# CAN_Bus.net
KiCad netlist of a schematic drawn in EAGLE
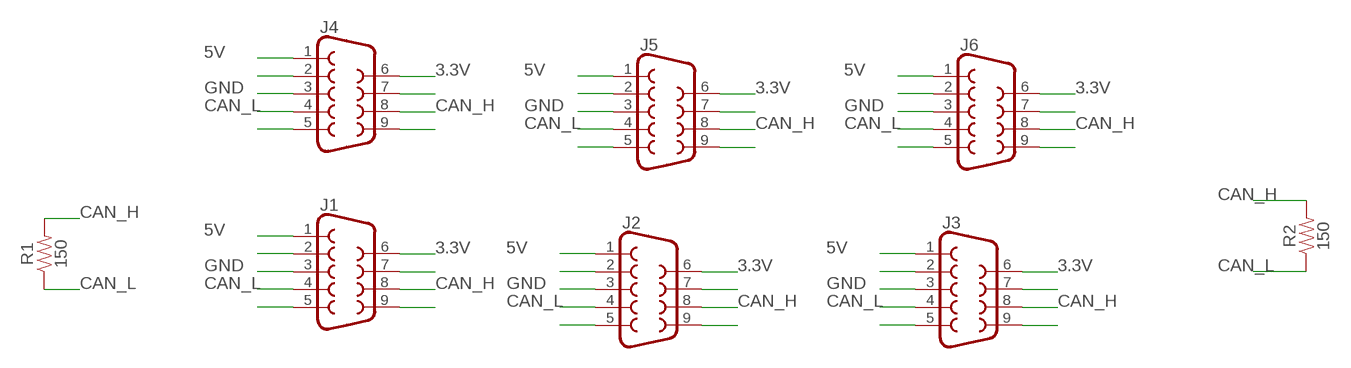
[diagram p0: schematic, sheet 1]

(export (version "E")
  (design (tool "Eeschema 10.0.6"))
  (components
    (comp (ref "J1")
      (value "DB9FEMALE")
      (footprint "eagle-import:DB9")
      (libsource (lib "eagle-import") (part "DB9FEMALE"))
    )
    (comp (ref "J2")
      (value "DB9FEMALE")
      (footprint "eagle-import:DB9")
      (libsource (lib "eagle-import") (part "DB9FEMALE"))
    )
    (comp (ref "J3")
      (value "DB9FEMALE")
      (footprint "eagle-import:DB9")
      (libsource (lib "eagle-import") (part "DB9FEMALE"))
    )
    (comp (ref "J4")
      (value "DB9FEMALE")
      (footprint "eagle-import:DB9")
      (libsource (lib "eagle-import") (part "DB9FEMALE"))
    )
    (comp (ref "J5")
      (value "DB9FEMALE")
      (footprint "eagle-import:DB9")
      (libsource (lib "eagle-import") (part "DB9FEMALE"))
    )
    (comp (ref "J6")
      (value "DB9FEMALE")
      (footprint "eagle-import:DB9")
      (libsource (lib "eagle-import") (part "DB9FEMALE"))
    )
    (comp (ref "R1")
      (value "150")
      (footprint "eagle-import:AXIAL-0.3")
      (libsource (lib "eagle-import") (part "100OHM-HORIZ-1/4W-1%"))
    )
    (comp (ref "R2")
      (value "150")
      (footprint "eagle-import:AXIAL-0.3")
      (libsource (lib "eagle-import") (part "100OHM-HORIZ-1/4W-1%"))
    )
  )
  (nets
    (net (code "1") (name "/3.3V") (class "Default")
      (node (ref "J1") (pin "6") (pinfunction "6_6") (pintype "passive"))
      (node (ref "J2") (pin "6") (pinfunction "6_6") (pintype "passive"))
      (node (ref "J3") (pin "6") (pinfunction "6_6") (pintype "passive"))
      (node (ref "J4") (pin "6") (pinfunction "6_6") (pintype "passive"))
      (node (ref "J5") (pin "6") (pinfunction "6_6") (pintype "passive"))
      (node (ref "J6") (pin "6") (pinfunction "6_6") (pintype "passive"))
    )
    (net (code "2") (name "/5V") (class "Default")
      (node (ref "J1") (pin "1") (pinfunction "1_1") (pintype "passive"))
      (node (ref "J2") (pin "1") (pinfunction "1_1") (pintype "passive"))
      (node (ref "J3") (pin "1") (pinfunction "1_1") (pintype "passive"))
      (node (ref "J4") (pin "1") (pinfunction "1_1") (pintype "passive"))
      (node (ref "J5") (pin "1") (pinfunction "1_1") (pintype "passive"))
      (node (ref "J6") (pin "1") (pinfunction "1_1") (pintype "passive"))
    )
    (net (code "3") (name "/CAN_H") (class "Default")
      (node (ref "J1") (pin "8") (pinfunction "8_8") (pintype "passive"))
      (node (ref "J2") (pin "8") (pinfunction "8_8") (pintype "passive"))
      (node (ref "J3") (pin "8") (pinfunction "8_8") (pintype "passive"))
      (node (ref "J4") (pin "8") (pinfunction "8_8") (pintype "passive"))
      (node (ref "J5") (pin "8") (pinfunction "8_8") (pintype "passive"))
      (node (ref "J6") (pin "8") (pinfunction "8_8") (pintype "passive"))
      (node (ref "R1") (pin "P$2") (pinfunction "2_P$2") (pintype "passive"))
      (node (ref "R2") (pin "P$2") (pinfunction "2_P$2") (pintype "passive"))
    )
    (net (code "4") (name "/CAN_L") (class "Default")
      (node (ref "J1") (pin "4") (pinfunction "4_4") (pintype "passive"))
      (node (ref "J2") (pin "4") (pinfunction "4_4") (pintype "passive"))
      (node (ref "J3") (pin "4") (pinfunction "4_4") (pintype "passive"))
      (node (ref "J4") (pin "4") (pinfunction "4_4") (pintype "passive"))
      (node (ref "J5") (pin "4") (pinfunction "4_4") (pintype "passive"))
      (node (ref "J6") (pin "4") (pinfunction "4_4") (pintype "passive"))
      (node (ref "R1") (pin "P$1") (pinfunction "1_P$1") (pintype "passive"))
      (node (ref "R2") (pin "P$1") (pinfunction "1_P$1") (pintype "passive"))
    )
    (net (code "5") (name "/GND") (class "Default")
      (node (ref "J1") (pin "3") (pinfunction "3_3") (pintype "passive"))
      (node (ref "J2") (pin "3") (pinfunction "3_3") (pintype "passive"))
      (node (ref "J3") (pin "3") (pinfunction "3_3") (pintype "passive"))
      (node (ref "J4") (pin "3") (pinfunction "3_3") (pintype "passive"))
      (node (ref "J5") (pin "3") (pinfunction "3_3") (pintype "passive"))
      (node (ref "J6") (pin "3") (pinfunction "3_3") (pintype "passive"))
    )
    (net (code "6") (name "unconnected-(J1-Pad2)") (class "Default")
      (node (ref "J1") (pin "2") (pinfunction "2_2") (pintype "passive"))
    )
    (net (code "7") (name "unconnected-(J1-Pad5)") (class "Default")
      (node (ref "J1") (pin "5") (pinfunction "5_5") (pintype "passive"))
    )
    (net (code "8") (name "unconnected-(J1-Pad7)") (class "Default")
      (node (ref "J1") (pin "7") (pinfunction "7_7") (pintype "passive"))
    )
    (net (code "9") (name "unconnected-(J1-Pad9)") (class "Default")
      (node (ref "J1") (pin "9") (pinfunction "9_9") (pintype "passive"))
    )
    (net (code "10") (name "unconnected-(J2-Pad2)") (class "Default")
      (node (ref "J2") (pin "2") (pinfunction "2_2") (pintype "passive"))
    )
    (net (code "11") (name "unconnected-(J2-Pad5)") (class "Default")
      (node (ref "J2") (pin "5") (pinfunction "5_5") (pintype "passive"))
    )
    (net (code "12") (name "unconnected-(J2-Pad7)") (class "Default")
      (node (ref "J2") (pin "7") (pinfunction "7_7") (pintype "passive"))
    )
    (net (code "13") (name "unconnected-(J2-Pad9)") (class "Default")
      (node (ref "J2") (pin "9") (pinfunction "9_9") (pintype "passive"))
    )
    (net (code "14") (name "unconnected-(J3-Pad2)") (class "Default")
      (node (ref "J3") (pin "2") (pinfunction "2_2") (pintype "passive"))
    )
    (net (code "15") (name "unconnected-(J3-Pad5)") (class "Default")
      (node (ref "J3") (pin "5") (pinfunction "5_5") (pintype "passive"))
    )
    (net (code "16") (name "unconnected-(J3-Pad7)") (class "Default")
      (node (ref "J3") (pin "7") (pinfunction "7_7") (pintype "passive"))
    )
    (net (code "17") (name "unconnected-(J3-Pad9)") (class "Default")
      (node (ref "J3") (pin "9") (pinfunction "9_9") (pintype "passive"))
    )
    (net (code "18") (name "unconnected-(J4-Pad2)") (class "Default")
      (node (ref "J4") (pin "2") (pinfunction "2_2") (pintype "passive"))
    )
    (net (code "19") (name "unconnected-(J4-Pad5)") (class "Default")
      (node (ref "J4") (pin "5") (pinfunction "5_5") (pintype "passive"))
    )
    (net (code "20") (name "unconnected-(J4-Pad7)") (class "Default")
      (node (ref "J4") (pin "7") (pinfunction "7_7") (pintype "passive"))
    )
    (net (code "21") (name "unconnected-(J4-Pad9)") (class "Default")
      (node (ref "J4") (pin "9") (pinfunction "9_9") (pintype "passive"))
    )
    (net (code "22") (name "unconnected-(J5-Pad2)") (class "Default")
      (node (ref "J5") (pin "2") (pinfunction "2_2") (pintype "passive"))
    )
    (net (code "23") (name "unconnected-(J5-Pad5)") (class "Default")
      (node (ref "J5") (pin "5") (pinfunction "5_5") (pintype "passive"))
    )
    (net (code "24") (name "unconnected-(J5-Pad7)") (class "Default")
      (node (ref "J5") (pin "7") (pinfunction "7_7") (pintype "passive"))
    )
    (net (code "25") (name "unconnected-(J5-Pad9)") (class "Default")
      (node (ref "J5") (pin "9") (pinfunction "9_9") (pintype "passive"))
    )
    (net (code "26") (name "unconnected-(J6-Pad2)") (class "Default")
      (node (ref "J6") (pin "2") (pinfunction "2_2") (pintype "passive"))
    )
    (net (code "27") (name "unconnected-(J6-Pad5)") (class "Default")
      (node (ref "J6") (pin "5") (pinfunction "5_5") (pintype "passive"))
    )
    (net (code "28") (name "unconnected-(J6-Pad7)") (class "Default")
      (node (ref "J6") (pin "7") (pinfunction "7_7") (pintype "passive"))
    )
    (net (code "29") (name "unconnected-(J6-Pad9)") (class "Default")
      (node (ref "J6") (pin "9") (pinfunction "9_9") (pintype "passive"))
    )
  )
)
